# esp32.net
KiCad netlist of a schematic drawn in Altium Designer
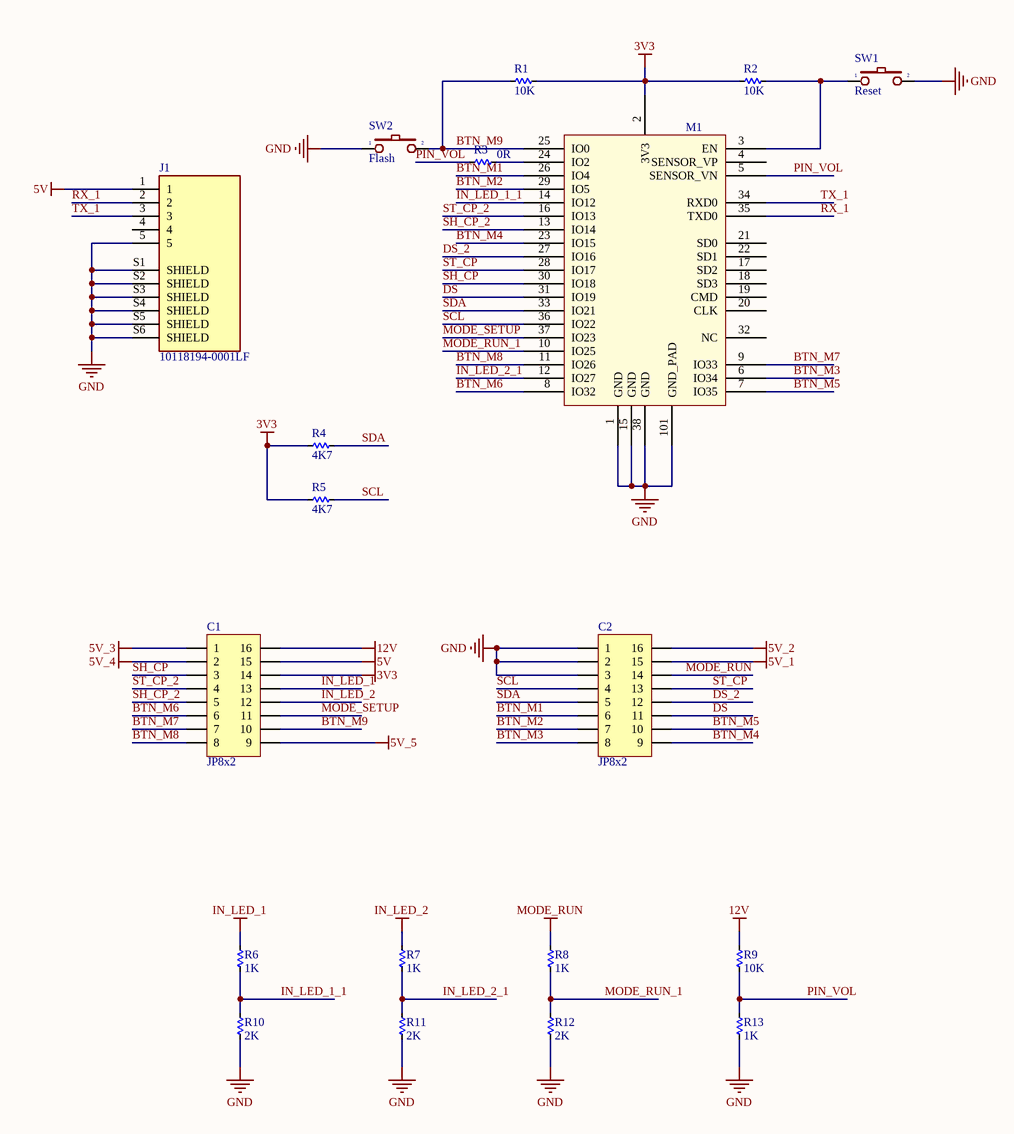
[diagram p0: esp32.SchDoc]

(export (version "E")
  (design (tool "Eeschema 10.0.6"))
  (components
    (comp (ref "C1")
      (value "JP8x2")
      (footprint "JP8-C2T")
      (description "WR-PHD 2.54 mm Dual Socket Header")
      (fields
        (field (name "MANUFACTURER") "Würth Elektronik eiSos GmbH")
        (field (name "PARTNO") "61301621821")
        (field (name "CREATED BY") "Karrer Zheng")
      )
      (libsource (lib "LIBRARY") (part "JP8x2"))
    )
    (comp (ref "C2")
      (value "JP8x2")
      (footprint "JP8-C2T")
      (description "WR-PHD 2.54 mm Dual Socket Header")
      (fields
        (field (name "MANUFACTURER") "Würth Elektronik eiSos GmbH")
        (field (name "PARTNO") "61301621821")
        (field (name "CREATED BY") "Karrer Zheng")
      )
      (libsource (lib "LIBRARY") (part "JP8x2"))
    )
    (comp (ref "J1")
      (value "10118194-0001LF")
      (footprint "AMPHENOL_10118194-0001LF")
      (description "USB - micro B USB 2.0 Receptacle Connector 5 Position Surface Mount, Right Angle; Through Hole")
      (fields (field (name "MF") "Amphenol ICC"))
      (libsource (lib "10118194-0001LF") (part "10118194-0001LF"))
    )
    (comp (ref "M1")
      (value "ESP32S_Module")
      (footprint "ESP32S")
      (description "Esp-32S")
      (libsource (lib "ESP32S") (part "ESP32S_Module"))
    )
    (comp (ref "R1")
      (value "10K")
      (footprint "RES-SMD-0603")
      (description "Resistor")
      (fields
        (field (name "MANUFACTURER") "Generic Components")
        (field (name "PUBLISHER") "Altium Hobart Technology Centre")
      )
      (libsource (lib "LIBRARY") (part "Res-SMD"))
    )
    (comp (ref "R2")
      (value "10K")
      (footprint "RES-SMD-0603")
      (description "Resistor")
      (fields
        (field (name "MANUFACTURER") "Generic Components")
        (field (name "PUBLISHER") "Altium Hobart Technology Centre")
      )
      (libsource (lib "LIBRARY") (part "Res-SMD"))
    )
    (comp (ref "R3")
      (value "0R")
      (footprint "RES-SMD-0603")
      (description "Resistor")
      (fields
        (field (name "MANUFACTURER") "Generic Components")
        (field (name "PUBLISHER") "Altium Hobart Technology Centre")
      )
      (libsource (lib "LIBRARY") (part "Res-SMD"))
    )
    (comp (ref "R4")
      (value "4K7")
      (footprint "RES-SMD-0603")
      (description "Resistor")
      (fields
        (field (name "MANUFACTURER") "Generic Components")
        (field (name "PUBLISHER") "Altium Hobart Technology Centre")
      )
      (libsource (lib "LIBRARY") (part "Res-SMD"))
    )
    (comp (ref "R5")
      (value "4K7")
      (footprint "RES-SMD-0603")
      (description "Resistor")
      (fields
        (field (name "MANUFACTURER") "Generic Components")
        (field (name "PUBLISHER") "Altium Hobart Technology Centre")
      )
      (libsource (lib "LIBRARY") (part "Res-SMD"))
    )
    (comp (ref "R6")
      (value "1K")
      (footprint "RES-SMD-0603")
      (description "Resistor")
      (fields
        (field (name "MANUFACTURER") "Generic Components")
        (field (name "PUBLISHER") "Altium Hobart Technology Centre")
      )
      (libsource (lib "LIBRARY") (part "Res-SMD"))
    )
    (comp (ref "R7")
      (value "1K")
      (footprint "RES-SMD-0603")
      (description "Resistor")
      (fields
        (field (name "MANUFACTURER") "Generic Components")
        (field (name "PUBLISHER") "Altium Hobart Technology Centre")
      )
      (libsource (lib "LIBRARY") (part "Res-SMD"))
    )
    (comp (ref "R8")
      (value "1K")
      (footprint "RES-SMD-0603")
      (description "Resistor")
      (fields
        (field (name "MANUFACTURER") "Generic Components")
        (field (name "PUBLISHER") "Altium Hobart Technology Centre")
      )
      (libsource (lib "LIBRARY") (part "Res-SMD"))
    )
    (comp (ref "R9")
      (value "10K")
      (footprint "RES-SMD-0603")
      (description "Resistor")
      (fields
        (field (name "MANUFACTURER") "Generic Components")
        (field (name "PUBLISHER") "Altium Hobart Technology Centre")
      )
      (libsource (lib "LIBRARY") (part "Res-SMD"))
    )
    (comp (ref "R10")
      (value "2K")
      (footprint "RES-SMD-0603")
      (description "Resistor")
      (fields
        (field (name "MANUFACTURER") "Generic Components")
        (field (name "PUBLISHER") "Altium Hobart Technology Centre")
      )
      (libsource (lib "LIBRARY") (part "Res-SMD"))
    )
    (comp (ref "R11")
      (value "2K")
      (footprint "RES-SMD-0603")
      (description "Resistor")
      (fields
        (field (name "MANUFACTURER") "Generic Components")
        (field (name "PUBLISHER") "Altium Hobart Technology Centre")
      )
      (libsource (lib "LIBRARY") (part "Res-SMD"))
    )
    (comp (ref "R12")
      (value "2K")
      (footprint "RES-SMD-0603")
      (description "Resistor")
      (fields
        (field (name "MANUFACTURER") "Generic Components")
        (field (name "PUBLISHER") "Altium Hobart Technology Centre")
      )
      (libsource (lib "LIBRARY") (part "Res-SMD"))
    )
    (comp (ref "R13")
      (value "1K")
      (footprint "RES-SMD-0603")
      (description "Resistor")
      (fields
        (field (name "MANUFACTURER") "Generic Components")
        (field (name "PUBLISHER") "Altium Hobart Technology Centre")
      )
      (libsource (lib "LIBRARY") (part "Res-SMD"))
    )
    (comp (ref "SW1")
      (value "Reset")
      (footprint "SW1-SMD")
      (description "Switch button 2 pin")
      (libsource (lib "LIBRARY") (part "SW2"))
    )
    (comp (ref "SW2")
      (value "Flash")
      (footprint "SW-DIP1-1")
      (description "Switch button 2 pin")
      (libsource (lib "LIBRARY") (part "SW2"))
    )
  )
  (nets
    (net (code "1") (name "/BTN_M1") (class "Default")
      (node (ref "C2") (pin "6") (pinfunction "6_6") (pintype "passive"))
      (node (ref "M1") (pin "26") (pinfunction "IO4_26") (pintype "passive"))
    )
    (net (code "2") (name "/BTN_M2") (class "Default")
      (node (ref "C2") (pin "7") (pinfunction "7_7") (pintype "passive"))
      (node (ref "M1") (pin "29") (pinfunction "IO5_29") (pintype "passive"))
    )
    (net (code "3") (name "/BTN_M3") (class "Default")
      (node (ref "C2") (pin "8") (pinfunction "8_8") (pintype "passive"))
      (node (ref "M1") (pin "6") (pinfunction "IO34_6") (pintype "passive"))
    )
    (net (code "4") (name "/BTN_M4") (class "Default")
      (node (ref "C2") (pin "9") (pinfunction "9_9") (pintype "passive"))
      (node (ref "M1") (pin "23") (pinfunction "IO15_23") (pintype "passive"))
    )
    (net (code "5") (name "/BTN_M5") (class "Default")
      (node (ref "C2") (pin "10") (pinfunction "10_10") (pintype "passive"))
      (node (ref "M1") (pin "7") (pinfunction "IO35_7") (pintype "passive"))
    )
    (net (code "6") (name "/BTN_M6") (class "Default")
      (node (ref "C1") (pin "6") (pinfunction "6_6") (pintype "passive"))
      (node (ref "M1") (pin "8") (pinfunction "IO32_8") (pintype "passive"))
    )
    (net (code "7") (name "/BTN_M7") (class "Default")
      (node (ref "C1") (pin "7") (pinfunction "7_7") (pintype "passive"))
      (node (ref "M1") (pin "9") (pinfunction "IO33_9") (pintype "passive"))
    )
    (net (code "8") (name "/BTN_M8") (class "Default")
      (node (ref "C1") (pin "8") (pinfunction "8_8") (pintype "passive"))
      (node (ref "M1") (pin "11") (pinfunction "IO26_11") (pintype "passive"))
    )
    (net (code "9") (name "/BTN_M9") (class "Default")
      (node (ref "C1") (pin "10") (pinfunction "10_10") (pintype "passive"))
      (node (ref "M1") (pin "25") (pinfunction "IO0_25") (pintype "passive"))
      (node (ref "R1") (pin "2") (pinfunction "2_2") (pintype "passive"))
      (node (ref "SW2") (pin "2") (pinfunction "2_2") (pintype "passive"))
    )
    (net (code "10") (name "/DS") (class "Default")
      (node (ref "C2") (pin "11") (pinfunction "11_11") (pintype "passive"))
      (node (ref "M1") (pin "31") (pinfunction "IO19_31") (pintype "passive"))
    )
    (net (code "11") (name "/DS_2") (class "Default")
      (node (ref "C2") (pin "12") (pinfunction "12_12") (pintype "passive"))
      (node (ref "M1") (pin "27") (pinfunction "IO16_27") (pintype "passive"))
    )
    (net (code "12") (name "/IN_LED_1_1") (class "Default")
      (node (ref "M1") (pin "14") (pinfunction "IO12_14") (pintype "passive"))
      (node (ref "R10") (pin "2") (pinfunction "2_2") (pintype "passive"))
      (node (ref "R6") (pin "1") (pinfunction "1_1") (pintype "passive"))
    )
    (net (code "13") (name "/IN_LED_2_1") (class "Default")
      (node (ref "M1") (pin "12") (pinfunction "IO27_12") (pintype "passive"))
      (node (ref "R11") (pin "2") (pinfunction "2_2") (pintype "passive"))
      (node (ref "R7") (pin "1") (pinfunction "1_1") (pintype "passive"))
    )
    (net (code "14") (name "/MODE_RUN_1") (class "Default")
      (node (ref "M1") (pin "10") (pinfunction "IO25_10") (pintype "passive"))
      (node (ref "R12") (pin "2") (pinfunction "2_2") (pintype "passive"))
      (node (ref "R8") (pin "1") (pinfunction "1_1") (pintype "passive"))
    )
    (net (code "15") (name "/MODE_SETUP") (class "Default")
      (node (ref "C1") (pin "11") (pinfunction "11_11") (pintype "passive"))
      (node (ref "M1") (pin "37") (pinfunction "IO23_37") (pintype "passive"))
    )
    (net (code "16") (name "/PIN_VOL") (class "Default")
      (node (ref "M1") (pin "5") (pinfunction "SENSOR_VN_5") (pintype "passive"))
      (node (ref "R13") (pin "2") (pinfunction "2_2") (pintype "passive"))
      (node (ref "R3") (pin "1") (pinfunction "1_1") (pintype "passive"))
      (node (ref "R9") (pin "1") (pinfunction "1_1") (pintype "passive"))
    )
    (net (code "17") (name "/RX_1") (class "Default")
      (node (ref "J1") (pin "2") (pinfunction "2_2") (pintype "passive"))
      (node (ref "M1") (pin "35") (pinfunction "TXD0_35") (pintype "passive"))
    )
    (net (code "18") (name "/SCL") (class "Default")
      (node (ref "C2") (pin "4") (pinfunction "4_4") (pintype "passive"))
      (node (ref "M1") (pin "36") (pinfunction "IO22_36") (pintype "passive"))
      (node (ref "R5") (pin "2") (pinfunction "2_2") (pintype "passive"))
    )
    (net (code "19") (name "/SDA") (class "Default")
      (node (ref "C2") (pin "5") (pinfunction "5_5") (pintype "passive"))
      (node (ref "M1") (pin "33") (pinfunction "IO21_33") (pintype "passive"))
      (node (ref "R4") (pin "2") (pinfunction "2_2") (pintype "passive"))
    )
    (net (code "20") (name "/SH_CP") (class "Default")
      (node (ref "C1") (pin "3") (pinfunction "3_3") (pintype "passive"))
      (node (ref "M1") (pin "30") (pinfunction "IO18_30") (pintype "passive"))
    )
    (net (code "21") (name "/SH_CP_2") (class "Default")
      (node (ref "C1") (pin "5") (pinfunction "5_5") (pintype "passive"))
      (node (ref "M1") (pin "13") (pinfunction "IO14_13") (pintype "passive"))
    )
    (net (code "22") (name "/ST_CP") (class "Default")
      (node (ref "C2") (pin "13") (pinfunction "13_13") (pintype "passive"))
      (node (ref "M1") (pin "28") (pinfunction "IO17_28") (pintype "passive"))
    )
    (net (code "23") (name "/ST_CP_2") (class "Default")
      (node (ref "C1") (pin "4") (pinfunction "4_4") (pintype "passive"))
      (node (ref "M1") (pin "16") (pinfunction "IO13_16") (pintype "passive"))
    )
    (net (code "24") (name "/TX_1") (class "Default")
      (node (ref "J1") (pin "3") (pinfunction "3_3") (pintype "passive"))
      (node (ref "M1") (pin "34") (pinfunction "RXD0_34") (pintype "passive"))
    )
    (net (code "25") (name "3V3") (class "Default")
      (node (ref "C1") (pin "14") (pinfunction "14_14") (pintype "passive"))
      (node (ref "M1") (pin "2") (pinfunction "3V3_2") (pintype "power_in"))
      (node (ref "R1") (pin "1") (pinfunction "1_1") (pintype "passive"))
      (node (ref "R2") (pin "2") (pinfunction "2_2") (pintype "passive"))
      (node (ref "R4") (pin "1") (pinfunction "1_1") (pintype "passive"))
      (node (ref "R5") (pin "1") (pinfunction "1_1") (pintype "passive"))
    )
    (net (code "26") (name "5V") (class "Default")
      (node (ref "C1") (pin "15") (pinfunction "15_15") (pintype "passive"))
      (node (ref "J1") (pin "1") (pinfunction "1_1") (pintype "passive"))
    )
    (net (code "27") (name "5V_1") (class "Default")
      (node (ref "C2") (pin "15") (pinfunction "15_15") (pintype "passive"))
    )
    (net (code "28") (name "5V_2") (class "Default")
      (node (ref "C2") (pin "16") (pinfunction "16_16") (pintype "passive"))
    )
    (net (code "29") (name "5V_3") (class "Default")
      (node (ref "C1") (pin "1") (pinfunction "1_1") (pintype "passive"))
    )
    (net (code "30") (name "5V_4") (class "Default")
      (node (ref "C1") (pin "2") (pinfunction "2_2") (pintype "passive"))
    )
    (net (code "31") (name "5V_5") (class "Default")
      (node (ref "C1") (pin "9") (pinfunction "9_9") (pintype "passive"))
    )
    (net (code "32") (name "12V") (class "Default")
      (node (ref "C1") (pin "16") (pinfunction "16_16") (pintype "passive"))
      (node (ref "R9") (pin "2") (pinfunction "2_2") (pintype "passive"))
    )
    (net (code "33") (name "GND") (class "Default")
      (node (ref "C2") (pin "1") (pinfunction "1_1") (pintype "passive"))
      (node (ref "C2") (pin "2") (pinfunction "2_2") (pintype "passive"))
      (node (ref "C2") (pin "3") (pinfunction "3_3") (pintype "passive"))
      (node (ref "J1") (pin "5") (pinfunction "5_5") (pintype "passive"))
      (node (ref "J1") (pin "S1") (pinfunction "SHIELD_S1") (pintype "passive"))
      (node (ref "J1") (pin "S2") (pinfunction "SHIELD_S2") (pintype "passive"))
      (node (ref "J1") (pin "S3") (pinfunction "SHIELD_S3") (pintype "passive"))
      (node (ref "J1") (pin "S4") (pinfunction "SHIELD_S4") (pintype "passive"))
      (node (ref "J1") (pin "S5") (pinfunction "SHIELD_S5") (pintype "passive"))
      (node (ref "J1") (pin "S6") (pinfunction "SHIELD_S6") (pintype "passive"))
      (node (ref "M1") (pin "1") (pinfunction "GND_1") (pintype "power_in"))
      (node (ref "M1") (pin "101") (pinfunction "GND_PAD_101") (pintype "power_in"))
      (node (ref "M1") (pin "15") (pinfunction "GND_15") (pintype "power_in"))
      (node (ref "M1") (pin "38") (pinfunction "GND_38") (pintype "power_in"))
      (node (ref "R10") (pin "1") (pinfunction "1_1") (pintype "passive"))
      (node (ref "R11") (pin "1") (pinfunction "1_1") (pintype "passive"))
      (node (ref "R12") (pin "1") (pinfunction "1_1") (pintype "passive"))
      (node (ref "R13") (pin "1") (pinfunction "1_1") (pintype "passive"))
      (node (ref "SW1") (pin "2") (pinfunction "2_2") (pintype "passive"))
      (node (ref "SW2") (pin "1") (pinfunction "1_1") (pintype "passive"))
    )
    (net (code "34") (name "IN_LED_1") (class "Default")
      (node (ref "C1") (pin "13") (pinfunction "13_13") (pintype "passive"))
      (node (ref "R6") (pin "2") (pinfunction "2_2") (pintype "passive"))
    )
    (net (code "35") (name "IN_LED_2") (class "Default")
      (node (ref "C1") (pin "12") (pinfunction "12_12") (pintype "passive"))
      (node (ref "R7") (pin "2") (pinfunction "2_2") (pintype "passive"))
    )
    (net (code "36") (name "MODE_RUN") (class "Default")
      (node (ref "C2") (pin "14") (pinfunction "14_14") (pintype "passive"))
      (node (ref "R8") (pin "2") (pinfunction "2_2") (pintype "passive"))
    )
    (net (code "37") (name "Net-(M1-EN)") (class "Default")
      (node (ref "M1") (pin "3") (pinfunction "EN_3") (pintype "power_in"))
      (node (ref "R2") (pin "1") (pinfunction "1_1") (pintype "passive"))
      (node (ref "SW1") (pin "1") (pinfunction "1_1") (pintype "passive"))
    )
    (net (code "38") (name "Net-(M1-IO2)") (class "Default")
      (node (ref "M1") (pin "24") (pinfunction "IO2_24") (pintype "passive"))
      (node (ref "R3") (pin "2") (pinfunction "2_2") (pintype "passive"))
    )
    (net (code "39") (name "unconnected-(J1-Pad4)") (class "Default")
      (node (ref "J1") (pin "4") (pinfunction "4_4") (pintype "passive"))
    )
    (net (code "40") (name "unconnected-(M1-CLK-Pad20)") (class "Default")
      (node (ref "M1") (pin "20") (pinfunction "CLK_20") (pintype "passive"))
    )
    (net (code "41") (name "unconnected-(M1-CMD-Pad19)") (class "Default")
      (node (ref "M1") (pin "19") (pinfunction "CMD_19") (pintype "passive"))
    )
    (net (code "42") (name "unconnected-(M1-NC-Pad32)") (class "Default")
      (node (ref "M1") (pin "32") (pinfunction "NC_32") (pintype "passive"))
    )
    (net (code "43") (name "unconnected-(M1-SD0-Pad21)") (class "Default")
      (node (ref "M1") (pin "21") (pinfunction "SD0_21") (pintype "passive"))
    )
    (net (code "44") (name "unconnected-(M1-SD1-Pad22)") (class "Default")
      (node (ref "M1") (pin "22") (pinfunction "SD1_22") (pintype "passive"))
    )
    (net (code "45") (name "unconnected-(M1-SD2-Pad17)") (class "Default")
      (node (ref "M1") (pin "17") (pinfunction "SD2_17") (pintype "passive"))
    )
    (net (code "46") (name "unconnected-(M1-SD3-Pad18)") (class "Default")
      (node (ref "M1") (pin "18") (pinfunction "SD3_18") (pintype "passive"))
    )
    (net (code "47") (name "unconnected-(M1-SENSOR_VP-Pad4)") (class "Default")
      (node (ref "M1") (pin "4") (pinfunction "SENSOR_VP_4") (pintype "passive"))
    )
  )
)
